# SCH_Hacker-Card_2024-08-31.net
KiCad netlist of a schematic drawn in EasyEDA
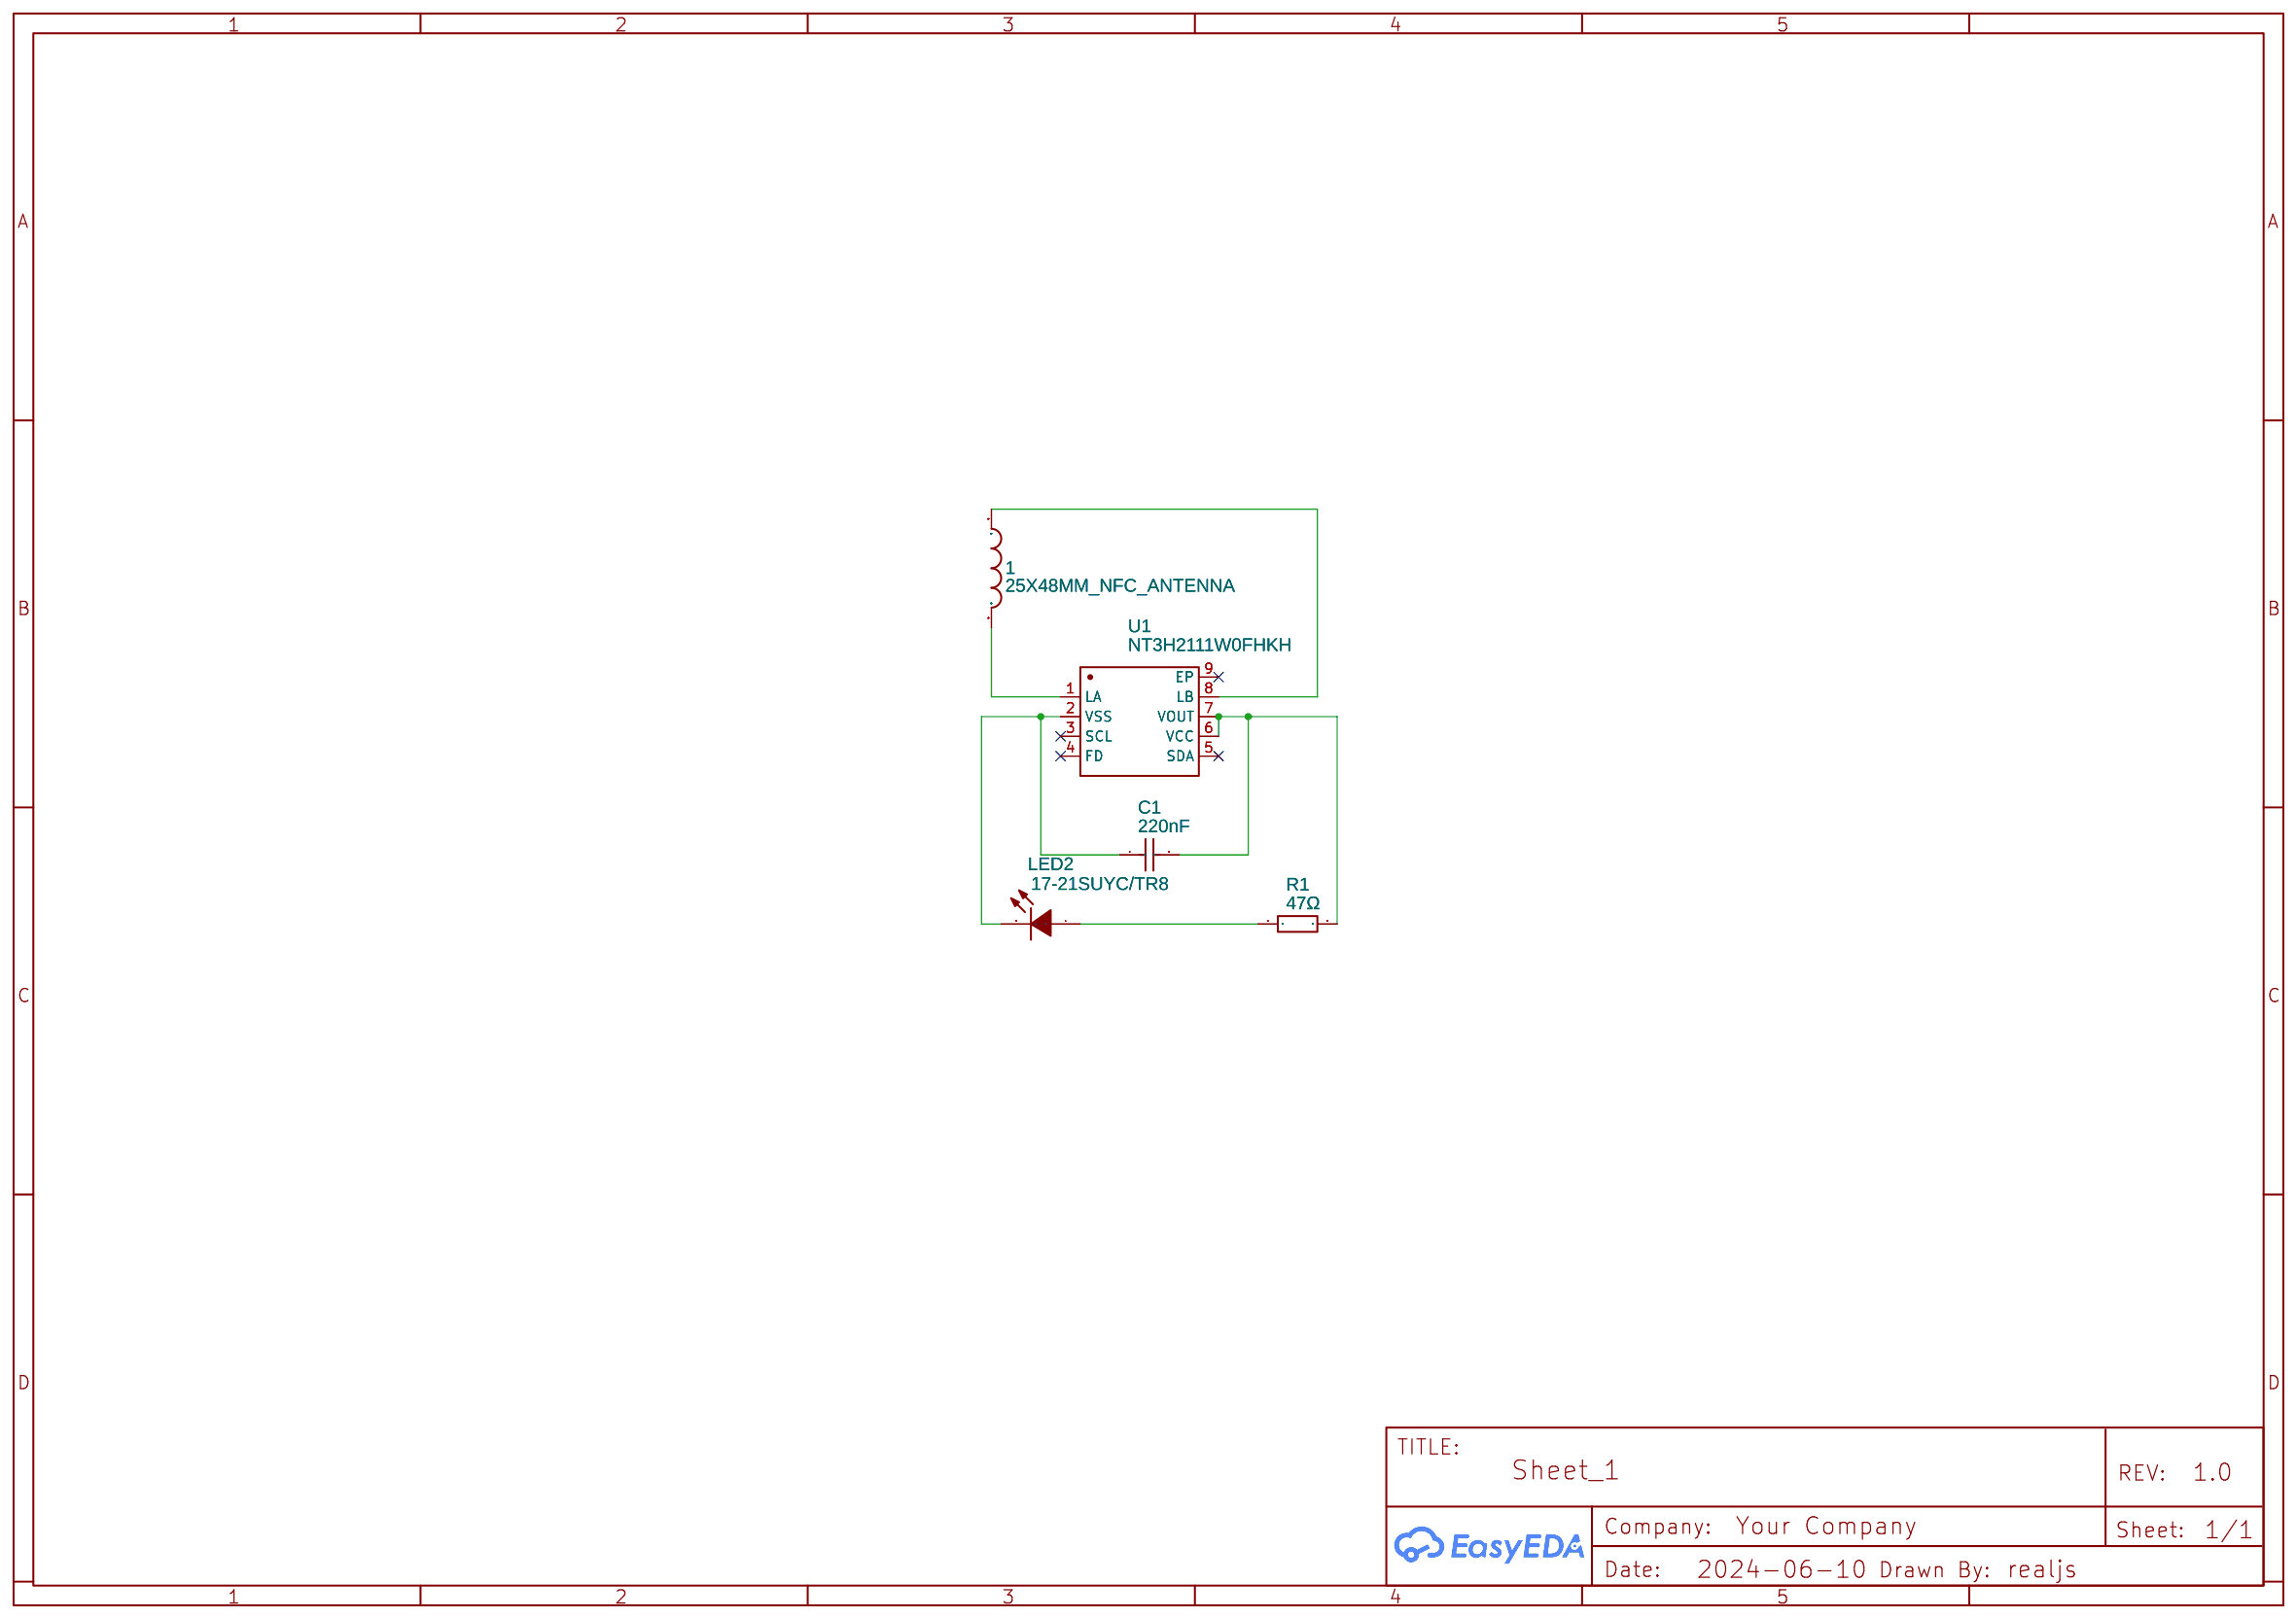
[diagram p0: schematic sheet]

(export (version "E")
  (design (tool "Eeschema 10.0.6"))
  (components
    (comp (ref "1") (value "25X48MM_NFC_ANTENNA") (libsource (lib "") (part "25X48MM_NFC_ANTENNA")))
    (comp (ref "C1")
      (value "220nF")
      (fields
        (field (name "Manufacturer Part") "CL10B224KA8NNNC")
        (field (name "Manufacturer") "SAMSUNG(三星)")
      )
      (libsource (lib "") (part "CL10B224KA8NNNC"))
    )
    (comp (ref "LED2")
      (value "17-21SUYC/TR8")
      (fields (field (name "Manufacturer Part") "KT-0805黄灯") (field (name "Manufacturer") "KENTO"))
      (libsource (lib "") (part "17-21SUYC/TR8"))
    )
    (comp (ref "R1")
      (value "47Ω")
      (fields
        (field (name "Manufacturer Part") "0603WAF470JT5E")
        (field (name "Manufacturer") "UNI-ROYAL(厚声)")
      )
      (libsource (lib "") (part "0603WAF470JT5E"))
    )
    (comp (ref "U1")
      (value "NT3H2111W0FHKH")
      (fields (field (name "Manufacturer") "NXP(恩智浦)"))
      (libsource (lib "") (part "NT3H2111W0FHKH"))
    )
  )
  (nets
    (net (code "1") (name "Net-(LED2-+)") (class "Default")
      (node (ref "LED2") (pin "1") (pinfunction "+_1") (pintype "unspecified"))
      (node (ref "R1") (pin "1") (pinfunction "1_1") (pintype "input"))
    )
    (net (code "2") (name "Net-(LED2--)") (class "Default")
      (node (ref "C1") (pin "1") (pinfunction "1_1") (pintype "input"))
      (node (ref "LED2") (pin "2") (pinfunction "-_2") (pintype "unspecified"))
      (node (ref "U1") (pin "2") (pinfunction "VSS_2") (pintype "unspecified"))
    )
    (net (code "3") (name "Net-(U1-LA)") (class "Default")
      (node (ref "1") (pin "P$2") (pinfunction "P$2_P$2") (pintype "bidirectional"))
      (node (ref "U1") (pin "1") (pinfunction "LA_1") (pintype "unspecified"))
    )
    (net (code "4") (name "Net-(U1-LB)") (class "Default")
      (node (ref "1") (pin "P$1") (pinfunction "P$1_P$1") (pintype "bidirectional"))
      (node (ref "U1") (pin "8") (pinfunction "LB_8") (pintype "unspecified"))
    )
    (net (code "5") (name "Net-(U1-VCC)") (class "Default")
      (node (ref "C1") (pin "2") (pinfunction "2_2") (pintype "input"))
      (node (ref "R1") (pin "2") (pinfunction "2_2") (pintype "input"))
      (node (ref "U1") (pin "6") (pinfunction "VCC_6") (pintype "unspecified"))
      (node (ref "U1") (pin "7") (pinfunction "VOUT_7") (pintype "unspecified"))
    )
    (net (code "6") (name "unconnected-(U1-EP-Pad9)") (class "Default")
      (node (ref "U1") (pin "9") (pinfunction "EP_9") (pintype "unspecified+no_connect"))
    )
    (net (code "7") (name "unconnected-(U1-FD-Pad4)") (class "Default")
      (node (ref "U1") (pin "4") (pinfunction "FD_4") (pintype "unspecified+no_connect"))
    )
    (net (code "8") (name "unconnected-(U1-SCL-Pad3)") (class "Default")
      (node (ref "U1") (pin "3") (pinfunction "SCL_3") (pintype "unspecified+no_connect"))
    )
    (net (code "9") (name "unconnected-(U1-SDA-Pad5)") (class "Default")
      (node (ref "U1") (pin "5") (pinfunction "SDA_5") (pintype "unspecified+no_connect"))
    )
  )
)
